# pulse-generator.net
KiCad netlist of a schematic drawn in EAGLE
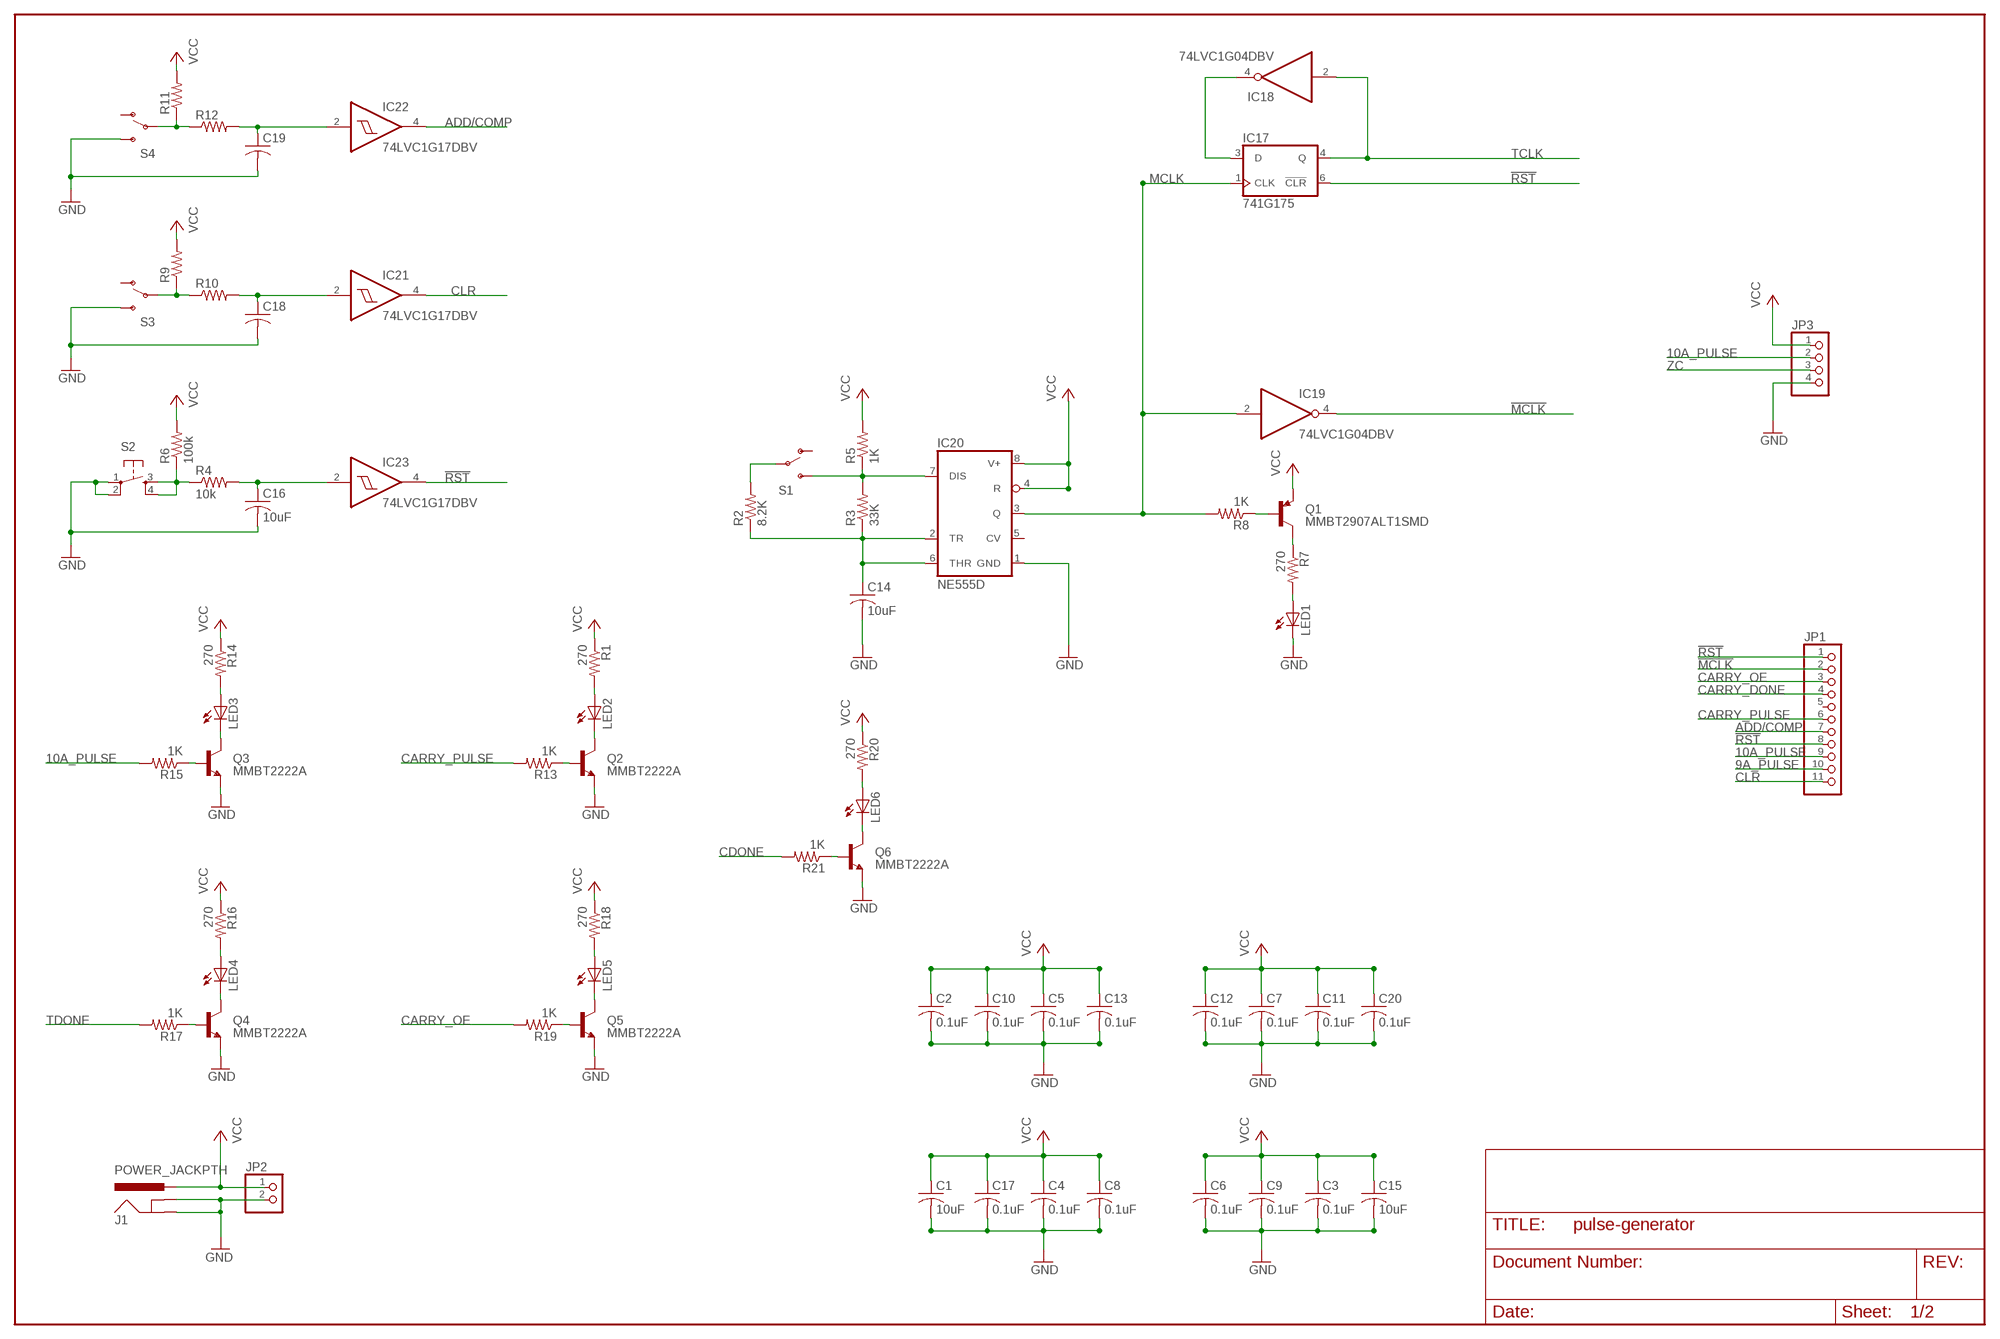
[diagram p0: schematic, sheet 1]
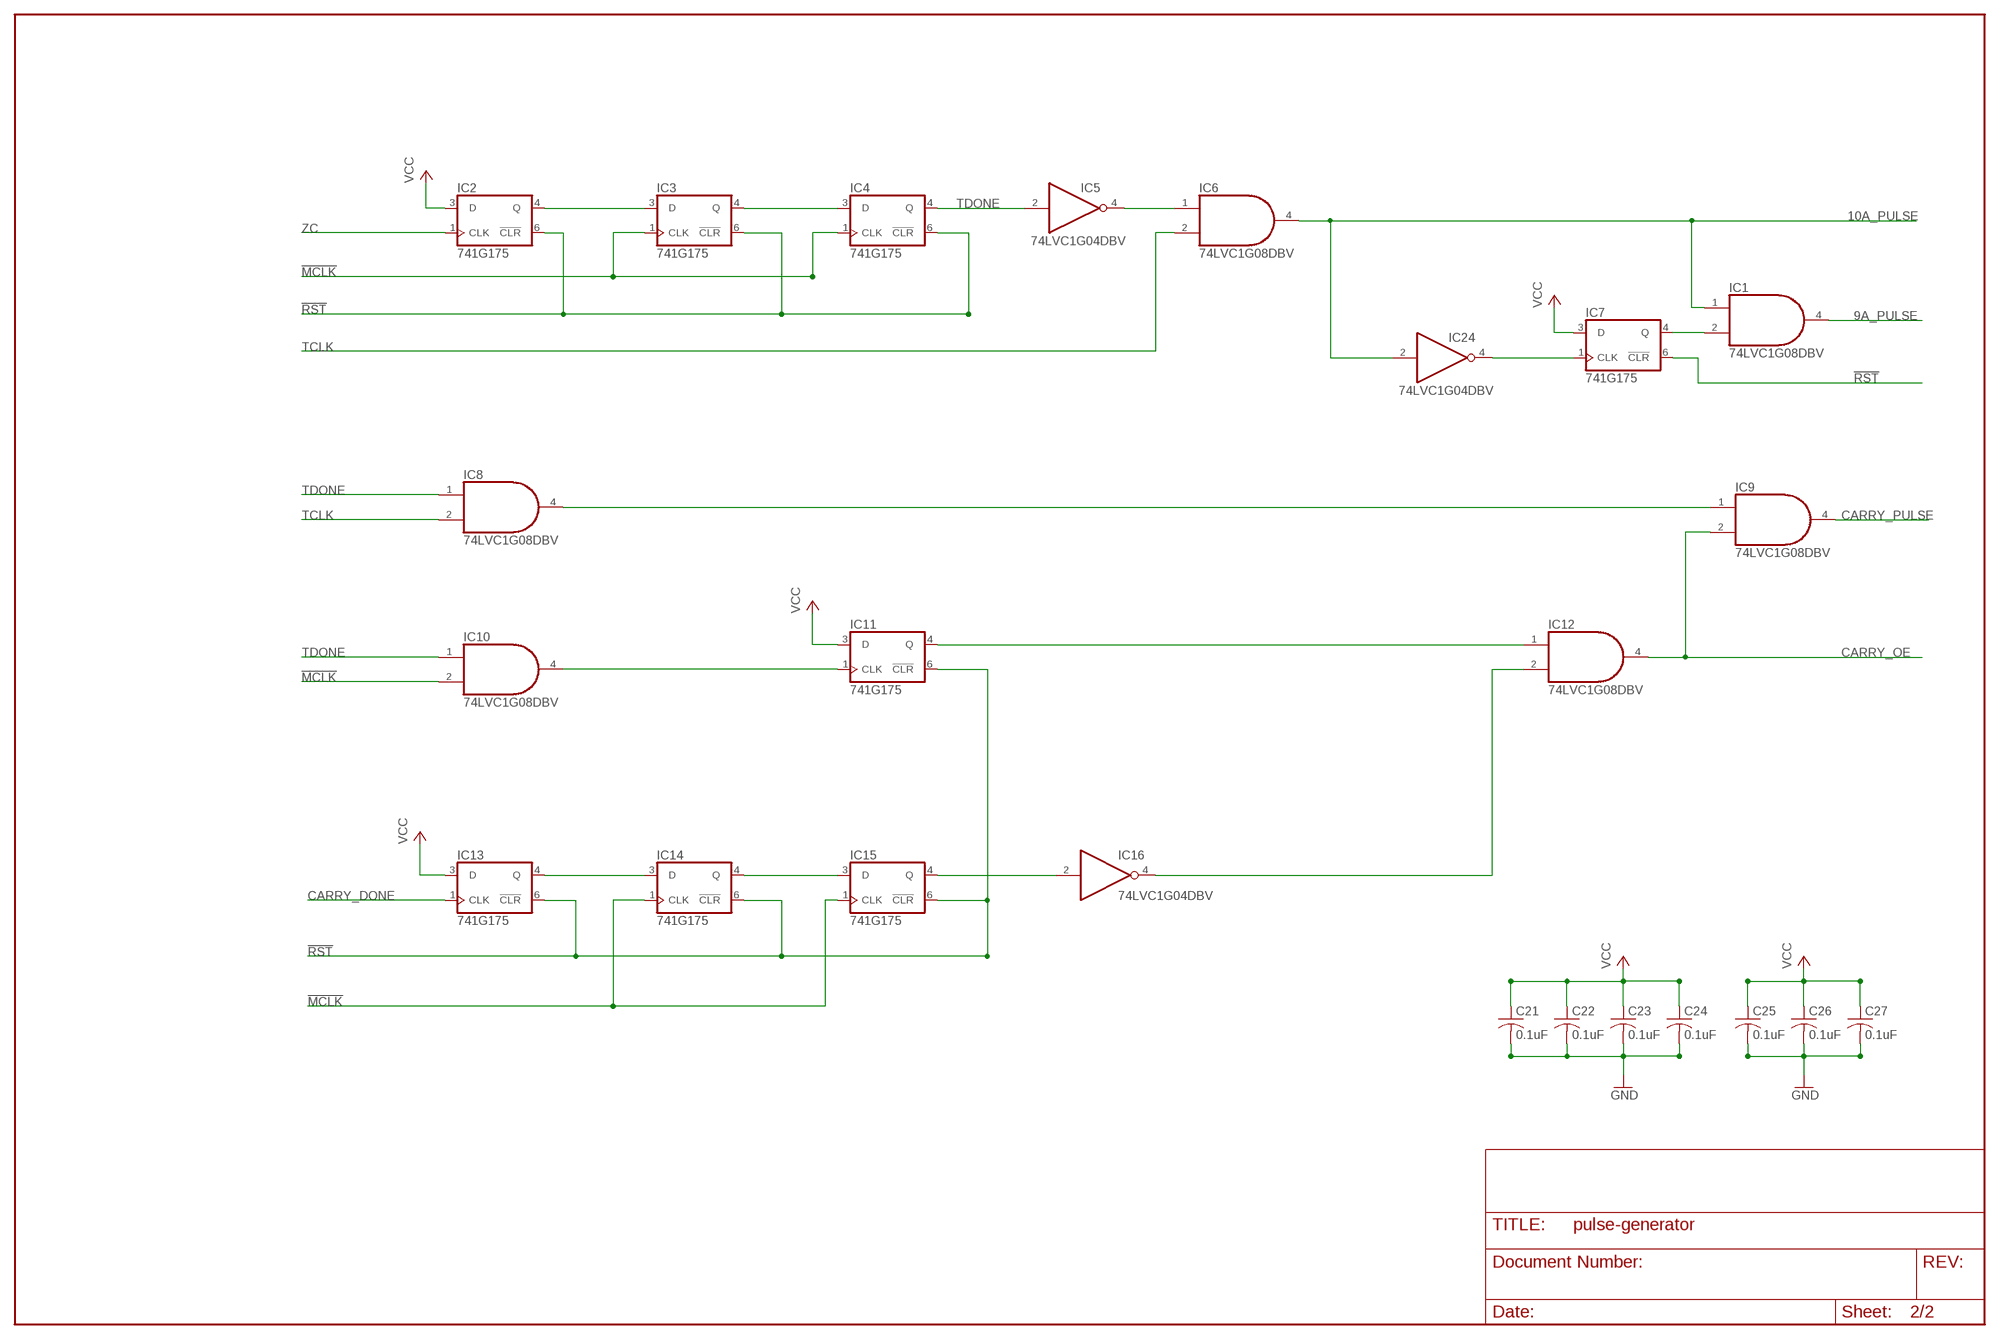
[diagram p1: schematic, sheet 2]

(export (version "E")
  (design (tool "Eeschema 10.0.6"))
  (components
    (comp (ref "C21")
      (value "0.1uF")
      (footprint "eagle-import:C0805")
      (libsource (lib "eagle-import") (part "C-USC0805"))
    )
    (comp (ref "C22")
      (value "0.1uF")
      (footprint "eagle-import:C0805")
      (libsource (lib "eagle-import") (part "C-USC0805"))
    )
    (comp (ref "C23")
      (value "0.1uF")
      (footprint "eagle-import:C0805")
      (libsource (lib "eagle-import") (part "C-USC0805"))
    )
    (comp (ref "C24")
      (value "0.1uF")
      (footprint "eagle-import:C0805")
      (libsource (lib "eagle-import") (part "C-USC0805"))
    )
    (comp (ref "C25")
      (value "0.1uF")
      (footprint "eagle-import:C0805")
      (libsource (lib "eagle-import") (part "C-USC0805"))
    )
    (comp (ref "C26")
      (value "0.1uF")
      (footprint "eagle-import:C0805")
      (libsource (lib "eagle-import") (part "C-USC0805"))
    )
    (comp (ref "C27")
      (value "0.1uF")
      (footprint "eagle-import:C0805")
      (libsource (lib "eagle-import") (part "C-USC0805"))
    )
    (comp (ref "IC1")
      (value "74LVC1G08DBV")
      (footprint "eagle-import:SOT23-5")
      (libsource (lib "eagle-import") (part "741G08DBVLVC"))
    )
    (comp (ref "IC2")
      (value "741G175")
      (footprint "eagle-import:DBV_R-PDSO-G6")
      (libsource (lib "eagle-import") (part "741G175"))
    )
    (comp (ref "IC3")
      (value "741G175")
      (footprint "eagle-import:DBV_R-PDSO-G6")
      (libsource (lib "eagle-import") (part "741G175"))
    )
    (comp (ref "IC4")
      (value "741G175")
      (footprint "eagle-import:DBV_R-PDSO-G6")
      (libsource (lib "eagle-import") (part "741G175"))
    )
    (comp (ref "IC5")
      (value "74LVC1G04DBV")
      (footprint "eagle-import:SOT23-5")
      (libsource (lib "eagle-import") (part "741G04DBVLVC"))
    )
    (comp (ref "IC6")
      (value "74LVC1G08DBV")
      (footprint "eagle-import:SOT23-5")
      (libsource (lib "eagle-import") (part "741G08DBVLVC"))
    )
    (comp (ref "IC7")
      (value "741G175")
      (footprint "eagle-import:DBV_R-PDSO-G6")
      (libsource (lib "eagle-import") (part "741G175"))
    )
    (comp (ref "IC8")
      (value "74LVC1G08DBV")
      (footprint "eagle-import:SOT23-5")
      (libsource (lib "eagle-import") (part "741G08DBVLVC"))
    )
    (comp (ref "IC9")
      (value "74LVC1G08DBV")
      (footprint "eagle-import:SOT23-5")
      (libsource (lib "eagle-import") (part "741G08DBVLVC"))
    )
    (comp (ref "IC10")
      (value "74LVC1G08DBV")
      (footprint "eagle-import:SOT23-5")
      (libsource (lib "eagle-import") (part "741G08DBVLVC"))
    )
    (comp (ref "IC11")
      (value "741G175")
      (footprint "eagle-import:DBV_R-PDSO-G6")
      (libsource (lib "eagle-import") (part "741G175"))
    )
    (comp (ref "IC12")
      (value "74LVC1G08DBV")
      (footprint "eagle-import:SOT23-5")
      (libsource (lib "eagle-import") (part "741G08DBVLVC"))
    )
    (comp (ref "IC13")
      (value "741G175")
      (footprint "eagle-import:DBV_R-PDSO-G6")
      (libsource (lib "eagle-import") (part "741G175"))
    )
    (comp (ref "IC14")
      (value "741G175")
      (footprint "eagle-import:DBV_R-PDSO-G6")
      (libsource (lib "eagle-import") (part "741G175"))
    )
    (comp (ref "IC15")
      (value "741G175")
      (footprint "eagle-import:DBV_R-PDSO-G6")
      (libsource (lib "eagle-import") (part "741G175"))
    )
    (comp (ref "IC16")
      (value "74LVC1G04DBV")
      (footprint "eagle-import:SOT23-5")
      (libsource (lib "eagle-import") (part "741G04DBVLVC"))
    )
    (comp (ref "IC24")
      (value "74LVC1G04DBV")
      (footprint "eagle-import:SOT23-5")
      (libsource (lib "eagle-import") (part "741G04DBVLVC"))
    )
    (comp (ref "C1")
      (value "10uF")
      (footprint "eagle-import:C0805")
      (libsource (lib "eagle-import") (part "C-USC0805"))
    )
    (comp (ref "C2")
      (value "0.1uF")
      (footprint "eagle-import:C0805")
      (libsource (lib "eagle-import") (part "C-USC0805"))
    )
    (comp (ref "C3")
      (value "0.1uF")
      (footprint "eagle-import:C0805")
      (libsource (lib "eagle-import") (part "C-USC0805"))
    )
    (comp (ref "C4")
      (value "0.1uF")
      (footprint "eagle-import:C0805")
      (libsource (lib "eagle-import") (part "C-USC0805"))
    )
    (comp (ref "C5")
      (value "0.1uF")
      (footprint "eagle-import:C0805")
      (libsource (lib "eagle-import") (part "C-USC0805"))
    )
    (comp (ref "C6")
      (value "0.1uF")
      (footprint "eagle-import:C0805")
      (libsource (lib "eagle-import") (part "C-USC0805"))
    )
    (comp (ref "C7")
      (value "0.1uF")
      (footprint "eagle-import:C0805")
      (libsource (lib "eagle-import") (part "C-USC0805"))
    )
    (comp (ref "C8")
      (value "0.1uF")
      (footprint "eagle-import:C0805")
      (libsource (lib "eagle-import") (part "C-USC0805"))
    )
    (comp (ref "C9")
      (value "0.1uF")
      (footprint "eagle-import:C0805")
      (libsource (lib "eagle-import") (part "C-USC0805"))
    )
    (comp (ref "C10")
      (value "0.1uF")
      (footprint "eagle-import:C0805")
      (libsource (lib "eagle-import") (part "C-USC0805"))
    )
    (comp (ref "C11")
      (value "0.1uF")
      (footprint "eagle-import:C0805")
      (libsource (lib "eagle-import") (part "C-USC0805"))
    )
    (comp (ref "C12")
      (value "0.1uF")
      (footprint "eagle-import:C0805")
      (libsource (lib "eagle-import") (part "C-USC0805"))
    )
    (comp (ref "C13")
      (value "0.1uF")
      (footprint "eagle-import:C0805")
      (libsource (lib "eagle-import") (part "C-USC0805"))
    )
    (comp (ref "C14")
      (value "10uF")
      (footprint "eagle-import:C0805")
      (libsource (lib "eagle-import") (part "C-USC0805"))
    )
    (comp (ref "C15")
      (value "10uF")
      (footprint "eagle-import:C0805")
      (libsource (lib "eagle-import") (part "C-USC0805"))
    )
    (comp (ref "C16")
      (value "10uF")
      (footprint "eagle-import:C0805")
      (libsource (lib "eagle-import") (part "C-USC0805"))
    )
    (comp (ref "C17")
      (value "0.1uF")
      (footprint "eagle-import:C0805")
      (libsource (lib "eagle-import") (part "C-USC0805"))
    )
    (comp (ref "C18")
      (value "C-USC0805")
      (footprint "eagle-import:C0805")
      (libsource (lib "eagle-import") (part "C-USC0805"))
    )
    (comp (ref "C19")
      (value "C-USC0805")
      (footprint "eagle-import:C0805")
      (libsource (lib "eagle-import") (part "C-USC0805"))
    )
    (comp (ref "C20")
      (value "0.1uF")
      (footprint "eagle-import:C0805")
      (libsource (lib "eagle-import") (part "C-USC0805"))
    )
    (comp (ref "IC17")
      (value "741G175")
      (footprint "eagle-import:DBV_R-PDSO-G6")
      (libsource (lib "eagle-import") (part "741G175"))
    )
    (comp (ref "IC18")
      (value "74LVC1G04DBV")
      (footprint "eagle-import:SOT23-5")
      (libsource (lib "eagle-import") (part "741G04DBVLVC"))
    )
    (comp (ref "IC19")
      (value "74LVC1G04DBV")
      (footprint "eagle-import:SOT23-5")
      (libsource (lib "eagle-import") (part "741G04DBVLVC"))
    )
    (comp (ref "IC20")
      (value "NE555D")
      (footprint "eagle-import:SO08")
      (libsource (lib "eagle-import") (part "555DNE"))
    )
    (comp (ref "IC21")
      (value "74LVC1G17DBV")
      (footprint "eagle-import:SOT23-5")
      (libsource (lib "eagle-import") (part "741G17DBVLVC"))
    )
    (comp (ref "IC22")
      (value "74LVC1G17DBV")
      (footprint "eagle-import:SOT23-5")
      (libsource (lib "eagle-import") (part "741G17DBVLVC"))
    )
    (comp (ref "IC23")
      (value "74LVC1G17DBV")
      (footprint "eagle-import:SOT23-5")
      (libsource (lib "eagle-import") (part "741G17DBVLVC"))
    )
    (comp (ref "J1")
      (value "POWER_JACKPTH")
      (footprint "eagle-import:POWER_JACK_PTH")
      (libsource (lib "eagle-import") (part "POWER_JACKPTH"))
    )
    (comp (ref "JP1")
      (value "PINHD-1X11")
      (footprint "eagle-import:1X11")
      (libsource (lib "eagle-import") (part "PINHD-1X11"))
    )
    (comp (ref "JP2")
      (value "PINHD-1X2")
      (footprint "eagle-import:1X02")
      (libsource (lib "eagle-import") (part "PINHD-1X2"))
    )
    (comp (ref "JP3")
      (value "PINHD-1X4")
      (footprint "eagle-import:1X04")
      (libsource (lib "eagle-import") (part "PINHD-1X4"))
    )
    (comp (ref "LED1")
      (value "LEDCHIP-LED0805")
      (footprint "eagle-import:CHIP-LED0805")
      (libsource (lib "eagle-import") (part "LEDCHIP-LED0805"))
    )
    (comp (ref "LED2")
      (value "LEDCHIP-LED0805")
      (footprint "eagle-import:CHIP-LED0805")
      (libsource (lib "eagle-import") (part "LEDCHIP-LED0805"))
    )
    (comp (ref "LED3")
      (value "LEDCHIP-LED0805")
      (footprint "eagle-import:CHIP-LED0805")
      (libsource (lib "eagle-import") (part "LEDCHIP-LED0805"))
    )
    (comp (ref "LED4")
      (value "LEDCHIP-LED0805")
      (footprint "eagle-import:CHIP-LED0805")
      (libsource (lib "eagle-import") (part "LEDCHIP-LED0805"))
    )
    (comp (ref "LED5")
      (value "LEDCHIP-LED0805")
      (footprint "eagle-import:CHIP-LED0805")
      (libsource (lib "eagle-import") (part "LEDCHIP-LED0805"))
    )
    (comp (ref "LED6")
      (value "LEDCHIP-LED0805")
      (footprint "eagle-import:CHIP-LED0805")
      (libsource (lib "eagle-import") (part "LEDCHIP-LED0805"))
    )
    (comp (ref "Q1")
      (value "MMBT2907ALT1SMD")
      (footprint "eagle-import:SOT23-BEC")
      (libsource (lib "eagle-import") (part "MMBT2907SMDALT1"))
    )
    (comp (ref "Q2")
      (value "MMBT2222A")
      (footprint "eagle-import:SOT23-3")
      (libsource (lib "eagle-import") (part "TRANSISTOR_NPNMMBT2222A"))
    )
    (comp (ref "Q3")
      (value "MMBT2222A")
      (footprint "eagle-import:SOT23-3")
      (libsource (lib "eagle-import") (part "TRANSISTOR_NPNMMBT2222A"))
    )
    (comp (ref "Q4")
      (value "MMBT2222A")
      (footprint "eagle-import:SOT23-3")
      (libsource (lib "eagle-import") (part "TRANSISTOR_NPNMMBT2222A"))
    )
    (comp (ref "Q5")
      (value "MMBT2222A")
      (footprint "eagle-import:SOT23-3")
      (libsource (lib "eagle-import") (part "TRANSISTOR_NPNMMBT2222A"))
    )
    (comp (ref "Q6")
      (value "MMBT2222A")
      (footprint "eagle-import:SOT23-3")
      (libsource (lib "eagle-import") (part "TRANSISTOR_NPNMMBT2222A"))
    )
    (comp (ref "R1")
      (value "270")
      (footprint "eagle-import:R0805")
      (libsource (lib "eagle-import") (part "R-US_R0805"))
    )
    (comp (ref "R2")
      (value "8.2K")
      (footprint "eagle-import:R0805")
      (libsource (lib "eagle-import") (part "R-US_R0805"))
    )
    (comp (ref "R3")
      (value "33K")
      (footprint "eagle-import:R0805")
      (libsource (lib "eagle-import") (part "R-US_R0805"))
    )
    (comp (ref "R4")
      (value "10k")
      (footprint "eagle-import:R0805")
      (libsource (lib "eagle-import") (part "R-US_R0805"))
    )
    (comp (ref "R5")
      (value "1K")
      (footprint "eagle-import:R0805")
      (libsource (lib "eagle-import") (part "R-US_R0805"))
    )
    (comp (ref "R6")
      (value "100k")
      (footprint "eagle-import:R0805")
      (libsource (lib "eagle-import") (part "R-US_R0805"))
    )
    (comp (ref "R7")
      (value "270")
      (footprint "eagle-import:R0805")
      (libsource (lib "eagle-import") (part "R-US_R0805"))
    )
    (comp (ref "R8")
      (value "1K")
      (footprint "eagle-import:R0805")
      (libsource (lib "eagle-import") (part "R-US_R0805"))
    )
    (comp (ref "R9")
      (value "R-US_R0805")
      (footprint "eagle-import:R0805")
      (libsource (lib "eagle-import") (part "R-US_R0805"))
    )
    (comp (ref "R10")
      (value "R-US_R0805")
      (footprint "eagle-import:R0805")
      (libsource (lib "eagle-import") (part "R-US_R0805"))
    )
    (comp (ref "R11")
      (value "R-US_R0805")
      (footprint "eagle-import:R0805")
      (libsource (lib "eagle-import") (part "R-US_R0805"))
    )
    (comp (ref "R12")
      (value "R-US_R0805")
      (footprint "eagle-import:R0805")
      (libsource (lib "eagle-import") (part "R-US_R0805"))
    )
    (comp (ref "R13")
      (value "1K")
      (footprint "eagle-import:R0805")
      (libsource (lib "eagle-import") (part "R-US_R0805"))
    )
    (comp (ref "R14")
      (value "270")
      (footprint "eagle-import:R0805")
      (libsource (lib "eagle-import") (part "R-US_R0805"))
    )
    (comp (ref "R15")
      (value "1K")
      (footprint "eagle-import:R0805")
      (libsource (lib "eagle-import") (part "R-US_R0805"))
    )
    (comp (ref "R16")
      (value "270")
      (footprint "eagle-import:R0805")
      (libsource (lib "eagle-import") (part "R-US_R0805"))
    )
    (comp (ref "R17")
      (value "1K")
      (footprint "eagle-import:R0805")
      (libsource (lib "eagle-import") (part "R-US_R0805"))
    )
    (comp (ref "R18")
      (value "270")
      (footprint "eagle-import:R0805")
      (libsource (lib "eagle-import") (part "R-US_R0805"))
    )
    (comp (ref "R19")
      (value "1K")
      (footprint "eagle-import:R0805")
      (libsource (lib "eagle-import") (part "R-US_R0805"))
    )
    (comp (ref "R20")
      (value "270")
      (footprint "eagle-import:R0805")
      (libsource (lib "eagle-import") (part "R-US_R0805"))
    )
    (comp (ref "R21")
      (value "1K")
      (footprint "eagle-import:R0805")
      (libsource (lib "eagle-import") (part "R-US_R0805"))
    )
    (comp (ref "S1")
      (value "SWITCH-SPDTPTH")
      (footprint "eagle-import:SWITCH-SPDT")
      (libsource (lib "eagle-import") (part "SWITCH-SPDTPTH"))
    )
    (comp (ref "S2")
      (value "TAC_SWITCHPTH")
      (footprint "eagle-import:TACTILE-PTH")
      (libsource (lib "eagle-import") (part "TAC_SWITCHPTH"))
    )
    (comp (ref "S3")
      (value "SWITCH-SPDTPTH")
      (footprint "eagle-import:SWITCH-SPDT")
      (libsource (lib "eagle-import") (part "SWITCH-SPDTPTH"))
    )
    (comp (ref "S4")
      (value "SWITCH-SPDTPTH")
      (footprint "eagle-import:SWITCH-SPDT")
      (libsource (lib "eagle-import") (part "SWITCH-SPDTPTH"))
    )
  )
  (nets
    (net (code "1") (name "9A_PULSE") (class "Default")
      (node (ref "IC1") (pin "4") (pinfunction "O_4") (pintype "output"))
      (node (ref "JP1") (pin "10") (pinfunction "10_10") (pintype "passive"))
    )
    (net (code "2") (name "10A_PULSE") (class "Default")
      (node (ref "IC1") (pin "1") (pinfunction "I0_1") (pintype "input"))
      (node (ref "IC24") (pin "2") (pinfunction "I_2") (pintype "input"))
      (node (ref "IC6") (pin "4") (pinfunction "O_4") (pintype "output"))
      (node (ref "JP1") (pin "9") (pinfunction "9_9") (pintype "passive"))
      (node (ref "JP3") (pin "2") (pinfunction "2_2") (pintype "passive"))
      (node (ref "R15") (pin "2") (pinfunction "2_2") (pintype "passive"))
    )
    (net (code "3") (name "ADD{slash}COMP") (class "Default")
      (node (ref "IC22") (pin "4") (pinfunction "O_4") (pintype "output"))
      (node (ref "JP1") (pin "7") (pinfunction "7_7") (pintype "passive"))
    )
    (net (code "4") (name "CARRY_DONE") (class "Default")
      (node (ref "IC13") (pin "1") (pinfunction "CLK_1") (pintype "input"))
      (node (ref "JP1") (pin "4") (pinfunction "4_4") (pintype "passive"))
    )
    (net (code "5") (name "CARRY_OE") (class "Default")
      (node (ref "IC12") (pin "4") (pinfunction "O_4") (pintype "output"))
      (node (ref "IC9") (pin "2") (pinfunction "I1_2") (pintype "input"))
      (node (ref "JP1") (pin "3") (pinfunction "3_3") (pintype "passive"))
      (node (ref "R19") (pin "2") (pinfunction "2_2") (pintype "passive"))
    )
    (net (code "6") (name "CARRY_PULSE") (class "Default")
      (node (ref "IC9") (pin "4") (pinfunction "O_4") (pintype "output"))
      (node (ref "JP1") (pin "6") (pinfunction "6_6") (pintype "passive"))
      (node (ref "R13") (pin "2") (pinfunction "2_2") (pintype "passive"))
    )
    (net (code "7") (name "CDONE") (class "Default")
      (node (ref "IC15") (pin "4") (pinfunction "Q_4") (pintype "output"))
      (node (ref "IC16") (pin "2") (pinfunction "I_2") (pintype "input"))
      (node (ref "R21") (pin "2") (pinfunction "2_2") (pintype "passive"))
    )
    (net (code "8") (name "CLR") (class "Default")
      (node (ref "IC21") (pin "4") (pinfunction "O_4") (pintype "output"))
      (node (ref "JP1") (pin "11") (pinfunction "11_11") (pintype "passive"))
    )
    (net (code "9") (name "GND") (class "Default")
      (node (ref "C1") (pin "2") (pinfunction "2_2") (pintype "passive"))
      (node (ref "C10") (pin "2") (pinfunction "2_2") (pintype "passive"))
      (node (ref "C11") (pin "2") (pinfunction "2_2") (pintype "passive"))
      (node (ref "C12") (pin "2") (pinfunction "2_2") (pintype "passive"))
      (node (ref "C13") (pin "2") (pinfunction "2_2") (pintype "passive"))
      (node (ref "C14") (pin "2") (pinfunction "2_2") (pintype "passive"))
      (node (ref "C15") (pin "2") (pinfunction "2_2") (pintype "passive"))
      (node (ref "C16") (pin "2") (pinfunction "2_2") (pintype "passive"))
      (node (ref "C17") (pin "2") (pinfunction "2_2") (pintype "passive"))
      (node (ref "C18") (pin "2") (pinfunction "2_2") (pintype "passive"))
      (node (ref "C19") (pin "2") (pinfunction "2_2") (pintype "passive"))
      (node (ref "C2") (pin "2") (pinfunction "2_2") (pintype "passive"))
      (node (ref "C20") (pin "2") (pinfunction "2_2") (pintype "passive"))
      (node (ref "C21") (pin "2") (pinfunction "2_2") (pintype "passive"))
      (node (ref "C22") (pin "2") (pinfunction "2_2") (pintype "passive"))
      (node (ref "C23") (pin "2") (pinfunction "2_2") (pintype "passive"))
      (node (ref "C24") (pin "2") (pinfunction "2_2") (pintype "passive"))
      (node (ref "C25") (pin "2") (pinfunction "2_2") (pintype "passive"))
      (node (ref "C26") (pin "2") (pinfunction "2_2") (pintype "passive"))
      (node (ref "C27") (pin "2") (pinfunction "2_2") (pintype "passive"))
      (node (ref "C3") (pin "2") (pinfunction "2_2") (pintype "passive"))
      (node (ref "C4") (pin "2") (pinfunction "2_2") (pintype "passive"))
      (node (ref "C5") (pin "2") (pinfunction "2_2") (pintype "passive"))
      (node (ref "C6") (pin "2") (pinfunction "2_2") (pintype "passive"))
      (node (ref "C7") (pin "2") (pinfunction "2_2") (pintype "passive"))
      (node (ref "C8") (pin "2") (pinfunction "2_2") (pintype "passive"))
      (node (ref "C9") (pin "2") (pinfunction "2_2") (pintype "passive"))
      (node (ref "IC20") (pin "1") (pinfunction "GND_1") (pintype "power_in"))
      (node (ref "J1") (pin "GND") (pinfunction "GND_GND") (pintype "bidirectional"))
      (node (ref "J1") (pin "GNDBREAK") (pinfunction "GNDBREAK_GNDBREAK") (pintype "bidirectional"))
      (node (ref "JP2") (pin "2") (pinfunction "2_2") (pintype "passive"))
      (node (ref "JP3") (pin "4") (pinfunction "4_4") (pintype "passive"))
      (node (ref "LED1") (pin "C") (pinfunction "C_C") (pintype "passive"))
      (node (ref "Q2") (pin "2") (pinfunction "E_2") (pintype "passive"))
      (node (ref "Q3") (pin "2") (pinfunction "E_2") (pintype "passive"))
      (node (ref "Q4") (pin "2") (pinfunction "E_2") (pintype "passive"))
      (node (ref "Q5") (pin "2") (pinfunction "E_2") (pintype "passive"))
      (node (ref "Q6") (pin "2") (pinfunction "E_2") (pintype "passive"))
      (node (ref "S2") (pin "1") (pinfunction "1_1") (pintype "passive"))
      (node (ref "S2") (pin "2") (pinfunction "2_2") (pintype "passive"))
      (node (ref "S3") (pin "3") (pinfunction "S_3") (pintype "passive"))
      (node (ref "S4") (pin "3") (pinfunction "S_3") (pintype "passive"))
    )
    (net (code "10") (name "MCLK") (class "Default")
      (node (ref "IC17") (pin "1") (pinfunction "CLK_1") (pintype "input"))
      (node (ref "IC19") (pin "2") (pinfunction "I_2") (pintype "input"))
      (node (ref "IC20") (pin "3") (pinfunction "Q_3") (pintype "output"))
      (node (ref "R8") (pin "2") (pinfunction "2_2") (pintype "passive"))
    )
    (net (code "11") (name "Net-(IC1A-I1)") (class "Default")
      (node (ref "IC1") (pin "2") (pinfunction "I1_2") (pintype "input"))
      (node (ref "IC7") (pin "4") (pinfunction "Q_4") (pintype "output"))
    )
    (net (code "12") (name "Net-(IC2A-Q)") (class "Default")
      (node (ref "IC2") (pin "4") (pinfunction "Q_4") (pintype "output"))
      (node (ref "IC3") (pin "3") (pinfunction "D_3") (pintype "input"))
    )
    (net (code "13") (name "Net-(IC3A-Q)") (class "Default")
      (node (ref "IC3") (pin "4") (pinfunction "Q_4") (pintype "output"))
      (node (ref "IC4") (pin "3") (pinfunction "D_3") (pintype "input"))
    )
    (net (code "14") (name "Net-(IC5A-O)") (class "Default")
      (node (ref "IC5") (pin "4") (pinfunction "O_4") (pintype "output"))
      (node (ref "IC6") (pin "1") (pinfunction "I0_1") (pintype "input"))
    )
    (net (code "15") (name "Net-(IC8A-O)") (class "Default")
      (node (ref "IC8") (pin "4") (pinfunction "O_4") (pintype "output"))
      (node (ref "IC9") (pin "1") (pinfunction "I0_1") (pintype "input"))
    )
    (net (code "16") (name "Net-(IC10A-O)") (class "Default")
      (node (ref "IC10") (pin "4") (pinfunction "O_4") (pintype "output"))
      (node (ref "IC11") (pin "1") (pinfunction "CLK_1") (pintype "input"))
    )
    (net (code "17") (name "Net-(IC11A-Q)") (class "Default")
      (node (ref "IC11") (pin "4") (pinfunction "Q_4") (pintype "output"))
      (node (ref "IC12") (pin "1") (pinfunction "I0_1") (pintype "input"))
    )
    (net (code "18") (name "Net-(IC12A-I1)") (class "Default")
      (node (ref "IC12") (pin "2") (pinfunction "I1_2") (pintype "input"))
      (node (ref "IC16") (pin "4") (pinfunction "O_4") (pintype "output"))
    )
    (net (code "19") (name "Net-(IC13A-Q)") (class "Default")
      (node (ref "IC13") (pin "4") (pinfunction "Q_4") (pintype "output"))
      (node (ref "IC14") (pin "3") (pinfunction "D_3") (pintype "input"))
    )
    (net (code "20") (name "Net-(IC14A-Q)") (class "Default")
      (node (ref "IC14") (pin "4") (pinfunction "Q_4") (pintype "output"))
      (node (ref "IC15") (pin "3") (pinfunction "D_3") (pintype "input"))
    )
    (net (code "21") (name "Net-(IC17A-D)") (class "Default")
      (node (ref "IC17") (pin "3") (pinfunction "D_3") (pintype "input"))
      (node (ref "IC18") (pin "4") (pinfunction "O_4") (pintype "output"))
    )
    (net (code "22") (name "Net-(IC20-DIS)") (class "Default")
      (node (ref "IC20") (pin "7") (pinfunction "DIS_7") (pintype "input"))
      (node (ref "R3") (pin "2") (pinfunction "2_2") (pintype "passive"))
      (node (ref "R5") (pin "1") (pinfunction "1_1") (pintype "passive"))
      (node (ref "S1") (pin "3") (pinfunction "S_3") (pintype "passive"))
    )
    (net (code "23") (name "Net-(IC20-THR)") (class "Default")
      (node (ref "C14") (pin "1") (pinfunction "1_1") (pintype "passive"))
      (node (ref "IC20") (pin "2") (pinfunction "TR_2") (pintype "input"))
      (node (ref "IC20") (pin "6") (pinfunction "THR_6") (pintype "input"))
      (node (ref "R2") (pin "1") (pinfunction "1_1") (pintype "passive"))
      (node (ref "R3") (pin "1") (pinfunction "1_1") (pintype "passive"))
    )
    (net (code "24") (name "Net-(IC21A-I)") (class "Default")
      (node (ref "C18") (pin "1") (pinfunction "1_1") (pintype "passive"))
      (node (ref "IC21") (pin "2") (pinfunction "I_2") (pintype "input"))
      (node (ref "R10") (pin "2") (pinfunction "2_2") (pintype "passive"))
    )
    (net (code "25") (name "Net-(IC22A-I)") (class "Default")
      (node (ref "C19") (pin "1") (pinfunction "1_1") (pintype "passive"))
      (node (ref "IC22") (pin "2") (pinfunction "I_2") (pintype "input"))
      (node (ref "R12") (pin "2") (pinfunction "2_2") (pintype "passive"))
    )
    (net (code "26") (name "Net-(IC23A-I)") (class "Default")
      (node (ref "C16") (pin "1") (pinfunction "1_1") (pintype "passive"))
      (node (ref "IC23") (pin "2") (pinfunction "I_2") (pintype "input"))
      (node (ref "R4") (pin "2") (pinfunction "2_2") (pintype "passive"))
    )
    (net (code "27") (name "Net-(IC24A-O)") (class "Default")
      (node (ref "IC24") (pin "4") (pinfunction "O_4") (pintype "output"))
      (node (ref "IC7") (pin "1") (pinfunction "CLK_1") (pintype "input"))
    )
    (net (code "28") (name "Net-(LED1-PadA)") (class "Default")
      (node (ref "LED1") (pin "A") (pinfunction "A_A") (pintype "passive"))
      (node (ref "R7") (pin "2") (pinfunction "2_2") (pintype "passive"))
    )
    (net (code "29") (name "Net-(LED2-PadA)") (class "Default")
      (node (ref "LED2") (pin "A") (pinfunction "A_A") (pintype "passive"))
      (node (ref "R1") (pin "2") (pinfunction "2_2") (pintype "passive"))
    )
    (net (code "30") (name "Net-(LED3-PadA)") (class "Default")
      (node (ref "LED3") (pin "A") (pinfunction "A_A") (pintype "passive"))
      (node (ref "R14") (pin "2") (pinfunction "2_2") (pintype "passive"))
    )
    (net (code "31") (name "Net-(LED4-PadA)") (class "Default")
      (node (ref "LED4") (pin "A") (pinfunction "A_A") (pintype "passive"))
      (node (ref "R16") (pin "2") (pinfunction "2_2") (pintype "passive"))
    )
    (net (code "32") (name "Net-(LED5-PadA)") (class "Default")
      (node (ref "LED5") (pin "A") (pinfunction "A_A") (pintype "passive"))
      (node (ref "R18") (pin "2") (pinfunction "2_2") (pintype "passive"))
    )
    (net (code "33") (name "Net-(LED6-PadA)") (class "Default")
      (node (ref "LED6") (pin "A") (pinfunction "A_A") (pintype "passive"))
      (node (ref "R20") (pin "2") (pinfunction "2_2") (pintype "passive"))
    )
    (net (code "34") (name "Net-(Q1-PadB)") (class "Default")
      (node (ref "Q1") (pin "B") (pinfunction "B_B") (pintype "passive"))
      (node (ref "R8") (pin "1") (pinfunction "1_1") (pintype "passive"))
    )
    (net (code "35") (name "Net-(Q1-PadC)") (class "Default")
      (node (ref "Q1") (pin "C") (pinfunction "C_C") (pintype "passive"))
      (node (ref "R7") (pin "1") (pinfunction "1_1") (pintype "passive"))
    )
    (net (code "36") (name "Net-(Q2-B)") (class "Default")
      (node (ref "Q2") (pin "1") (pinfunction "B_1") (pintype "passive"))
      (node (ref "R13") (pin "1") (pinfunction "1_1") (pintype "passive"))
    )
    (net (code "37") (name "Net-(Q2-C)") (class "Default")
      (node (ref "LED2") (pin "C") (pinfunction "C_C") (pintype "passive"))
      (node (ref "Q2") (pin "3") (pinfunction "C_3") (pintype "passive"))
    )
    (net (code "38") (name "Net-(Q3-B)") (class "Default")
      (node (ref "Q3") (pin "1") (pinfunction "B_1") (pintype "passive"))
      (node (ref "R15") (pin "1") (pinfunction "1_1") (pintype "passive"))
    )
    (net (code "39") (name "Net-(Q3-C)") (class "Default")
      (node (ref "LED3") (pin "C") (pinfunction "C_C") (pintype "passive"))
      (node (ref "Q3") (pin "3") (pinfunction "C_3") (pintype "passive"))
    )
    (net (code "40") (name "Net-(Q4-B)") (class "Default")
      (node (ref "Q4") (pin "1") (pinfunction "B_1") (pintype "passive"))
      (node (ref "R17") (pin "1") (pinfunction "1_1") (pintype "passive"))
    )
    (net (code "41") (name "Net-(Q4-C)") (class "Default")
      (node (ref "LED4") (pin "C") (pinfunction "C_C") (pintype "passive"))
      (node (ref "Q4") (pin "3") (pinfunction "C_3") (pintype "passive"))
    )
    (net (code "42") (name "Net-(Q5-B)") (class "Default")
      (node (ref "Q5") (pin "1") (pinfunction "B_1") (pintype "passive"))
      (node (ref "R19") (pin "1") (pinfunction "1_1") (pintype "passive"))
    )
    (net (code "43") (name "Net-(Q5-C)") (class "Default")
      (node (ref "LED5") (pin "C") (pinfunction "C_C") (pintype "passive"))
      (node (ref "Q5") (pin "3") (pinfunction "C_3") (pintype "passive"))
    )
    (net (code "44") (name "Net-(Q6-B)") (class "Default")
      (node (ref "Q6") (pin "1") (pinfunction "B_1") (pintype "passive"))
      (node (ref "R21") (pin "1") (pinfunction "1_1") (pintype "passive"))
    )
    (net (code "45") (name "Net-(Q6-C)") (class "Default")
      (node (ref "LED6") (pin "C") (pinfunction "C_C") (pintype "passive"))
      (node (ref "Q6") (pin "3") (pinfunction "C_3") (pintype "passive"))
    )
    (net (code "46") (name "Net-(R4-Pad1)") (class "Default")
      (node (ref "R4") (pin "1") (pinfunction "1_1") (pintype "passive"))
      (node (ref "R6") (pin "1") (pinfunction "1_1") (pintype "passive"))
      (node (ref "S2") (pin "3") (pinfunction "3_3") (pintype "passive"))
      (node (ref "S2") (pin "4") (pinfunction "4_4") (pintype "passive"))
    )
    (net (code "47") (name "Net-(S1-P)") (class "Default")
      (node (ref "R2") (pin "2") (pinfunction "2_2") (pintype "passive"))
      (node (ref "S1") (pin "2") (pinfunction "P_2") (pintype "passive"))
    )
    (net (code "48") (name "Net-(S3-P)") (class "Default")
      (node (ref "R10") (pin "1") (pinfunction "1_1") (pintype "passive"))
      (node (ref "R9") (pin "1") (pinfunction "1_1") (pintype "passive"))
      (node (ref "S3") (pin "2") (pinfunction "P_2") (pintype "passive"))
    )
    (net (code "49") (name "Net-(S4-P)") (class "Default")
      (node (ref "R11") (pin "1") (pinfunction "1_1") (pintype "passive"))
      (node (ref "R12") (pin "1") (pinfunction "1_1") (pintype "passive"))
      (node (ref "S4") (pin "2") (pinfunction "P_2") (pintype "passive"))
    )
    (net (code "50") (name "TCLK") (class "Default")
      (node (ref "IC17") (pin "4") (pinfunction "Q_4") (pintype "output"))
      (node (ref "IC18") (pin "2") (pinfunction "I_2") (pintype "input"))
      (node (ref "IC6") (pin "2") (pinfunction "I1_2") (pintype "input"))
      (node (ref "IC8") (pin "2") (pinfunction "I1_2") (pintype "input"))
    )
    (net (code "51") (name "TDONE") (class "Default")
      (node (ref "IC10") (pin "1") (pinfunction "I0_1") (pintype "input"))
      (node (ref "IC4") (pin "4") (pinfunction "Q_4") (pintype "output"))
      (node (ref "IC5") (pin "2") (pinfunction "I_2") (pintype "input"))
      (node (ref "IC8") (pin "1") (pinfunction "I0_1") (pintype "input"))
      (node (ref "R17") (pin "2") (pinfunction "2_2") (pintype "passive"))
    )
    (net (code "52") (name "VCC") (class "Default")
      (node (ref "C1") (pin "1") (pinfunction "1_1") (pintype "passive"))
      (node (ref "C10") (pin "1") (pinfunction "1_1") (pintype "passive"))
      (node (ref "C11") (pin "1") (pinfunction "1_1") (pintype "passive"))
      (node (ref "C12") (pin "1") (pinfunction "1_1") (pintype "passive"))
      (node (ref "C13") (pin "1") (pinfunction "1_1") (pintype "passive"))
      (node (ref "C15") (pin "1") (pinfunction "1_1") (pintype "passive"))
      (node (ref "C17") (pin "1") (pinfunction "1_1") (pintype "passive"))
      (node (ref "C2") (pin "1") (pinfunction "1_1") (pintype "passive"))
      (node (ref "C20") (pin "1") (pinfunction "1_1") (pintype "passive"))
      (node (ref "C21") (pin "1") (pinfunction "1_1") (pintype "passive"))
      (node (ref "C22") (pin "1") (pinfunction "1_1") (pintype "passive"))
      (node (ref "C23") (pin "1") (pinfunction "1_1") (pintype "passive"))
      (node (ref "C24") (pin "1") (pinfunction "1_1") (pintype "passive"))
      (node (ref "C25") (pin "1") (pinfunction "1_1") (pintype "passive"))
      (node (ref "C26") (pin "1") (pinfunction "1_1") (pintype "passive"))
      (node (ref "C27") (pin "1") (pinfunction "1_1") (pintype "passive"))
      (node (ref "C3") (pin "1") (pinfunction "1_1") (pintype "passive"))
      (node (ref "C4") (pin "1") (pinfunction "1_1") (pintype "passive"))
      (node (ref "C5") (pin "1") (pinfunction "1_1") (pintype "passive"))
      (node (ref "C6") (pin "1") (pinfunction "1_1") (pintype "passive"))
      (node (ref "C7") (pin "1") (pinfunction "1_1") (pintype "passive"))
      (node (ref "C8") (pin "1") (pinfunction "1_1") (pintype "passive"))
      (node (ref "C9") (pin "1") (pinfunction "1_1") (pintype "passive"))
      (node (ref "IC11") (pin "3") (pinfunction "D_3") (pintype "input"))
      (node (ref "IC13") (pin "3") (pinfunction "D_3") (pintype "input"))
      (node (ref "IC2") (pin "3") (pinfunction "D_3") (pintype "input"))
      (node (ref "IC20") (pin "4") (pinfunction "R_4") (pintype "input"))
      (node (ref "IC20") (pin "8") (pinfunction "V+_8") (pintype "power_in"))
      (node (ref "IC7") (pin "3") (pinfunction "D_3") (pintype "input"))
      (node (ref "J1") (pin "PWR") (pinfunction "PWR_PWR") (pintype "bidirectional"))
      (node (ref "JP2") (pin "1") (pinfunction "1_1") (pintype "passive"))
      (node (ref "JP3") (pin "1") (pinfunction "1_1") (pintype "passive"))
      (node (ref "Q1") (pin "E") (pinfunction "E_E") (pintype "passive"))
      (node (ref "R1") (pin "1") (pinfunction "1_1") (pintype "passive"))
      (node (ref "R11") (pin "2") (pinfunction "2_2") (pintype "passive"))
      (node (ref "R14") (pin "1") (pinfunction "1_1") (pintype "passive"))
      (node (ref "R16") (pin "1") (pinfunction "1_1") (pintype "passive"))
      (node (ref "R18") (pin "1") (pinfunction "1_1") (pintype "passive"))
      (node (ref "R20") (pin "1") (pinfunction "1_1") (pintype "passive"))
      (node (ref "R5") (pin "2") (pinfunction "2_2") (pintype "passive"))
      (node (ref "R6") (pin "2") (pinfunction "2_2") (pintype "passive"))
      (node (ref "R9") (pin "2") (pinfunction "2_2") (pintype "passive"))
    )
    (net (code "53") (name "ZC") (class "Default")
      (node (ref "IC2") (pin "1") (pinfunction "CLK_1") (pintype "input"))
      (node (ref "JP3") (pin "3") (pinfunction "3_3") (pintype "passive"))
    )
    (net (code "54") (name "unconnected-(IC20-CV-Pad5)") (class "Default")
      (node (ref "IC20") (pin "5") (pinfunction "CV_5") (pintype "input"))
    )
    (net (code "55") (name "unconnected-(JP1-Pad5)") (class "Default")
      (node (ref "JP1") (pin "5") (pinfunction "5_5") (pintype "passive"))
    )
    (net (code "56") (name "unconnected-(S1-O-Pad1)") (class "Default")
      (node (ref "S1") (pin "1") (pinfunction "O_1") (pintype "passive"))
    )
    (net (code "57") (name "unconnected-(S3-O-Pad1)") (class "Default")
      (node (ref "S3") (pin "1") (pinfunction "O_1") (pintype "passive"))
    )
    (net (code "58") (name "unconnected-(S4-O-Pad1)") (class "Default")
      (node (ref "S4") (pin "1") (pinfunction "O_1") (pintype "passive"))
    )
    (net (code "59") (name "~{MCLK}") (class "Default")
      (node (ref "IC10") (pin "2") (pinfunction "I1_2") (pintype "input"))
      (node (ref "IC14") (pin "1") (pinfunction "CLK_1") (pintype "input"))
      (node (ref "IC15") (pin "1") (pinfunction "CLK_1") (pintype "input"))
      (node (ref "IC19") (pin "4") (pinfunction "O_4") (pintype "output"))
      (node (ref "IC3") (pin "1") (pinfunction "CLK_1") (pintype "input"))
      (node (ref "IC4") (pin "1") (pinfunction "CLK_1") (pintype "input"))
      (node (ref "JP1") (pin "2") (pinfunction "2_2") (pintype "passive"))
    )
    (net (code "60") (name "~{RST}") (class "Default")
      (node (ref "IC11") (pin "6") (pinfunction "~{CLR}_6") (pintype "input"))
      (node (ref "IC13") (pin "6") (pinfunction "~{CLR}_6") (pintype "input"))
      (node (ref "IC14") (pin "6") (pinfunction "~{CLR}_6") (pintype "input"))
      (node (ref "IC15") (pin "6") (pinfunction "~{CLR}_6") (pintype "input"))
      (node (ref "IC17") (pin "6") (pinfunction "~{CLR}_6") (pintype "input"))
      (node (ref "IC2") (pin "6") (pinfunction "~{CLR}_6") (pintype "input"))
      (node (ref "IC23") (pin "4") (pinfunction "O_4") (pintype "output"))
      (node (ref "IC3") (pin "6") (pinfunction "~{CLR}_6") (pintype "input"))
      (node (ref "IC4") (pin "6") (pinfunction "~{CLR}_6") (pintype "input"))
      (node (ref "IC7") (pin "6") (pinfunction "~{CLR}_6") (pintype "input"))
      (node (ref "JP1") (pin "1") (pinfunction "1_1") (pintype "passive"))
      (node (ref "JP1") (pin "8") (pinfunction "8_8") (pintype "passive"))
    )
  )
)
